# MultiChannelADC.net
KiCad netlist of a schematic drawn in Altium Designer
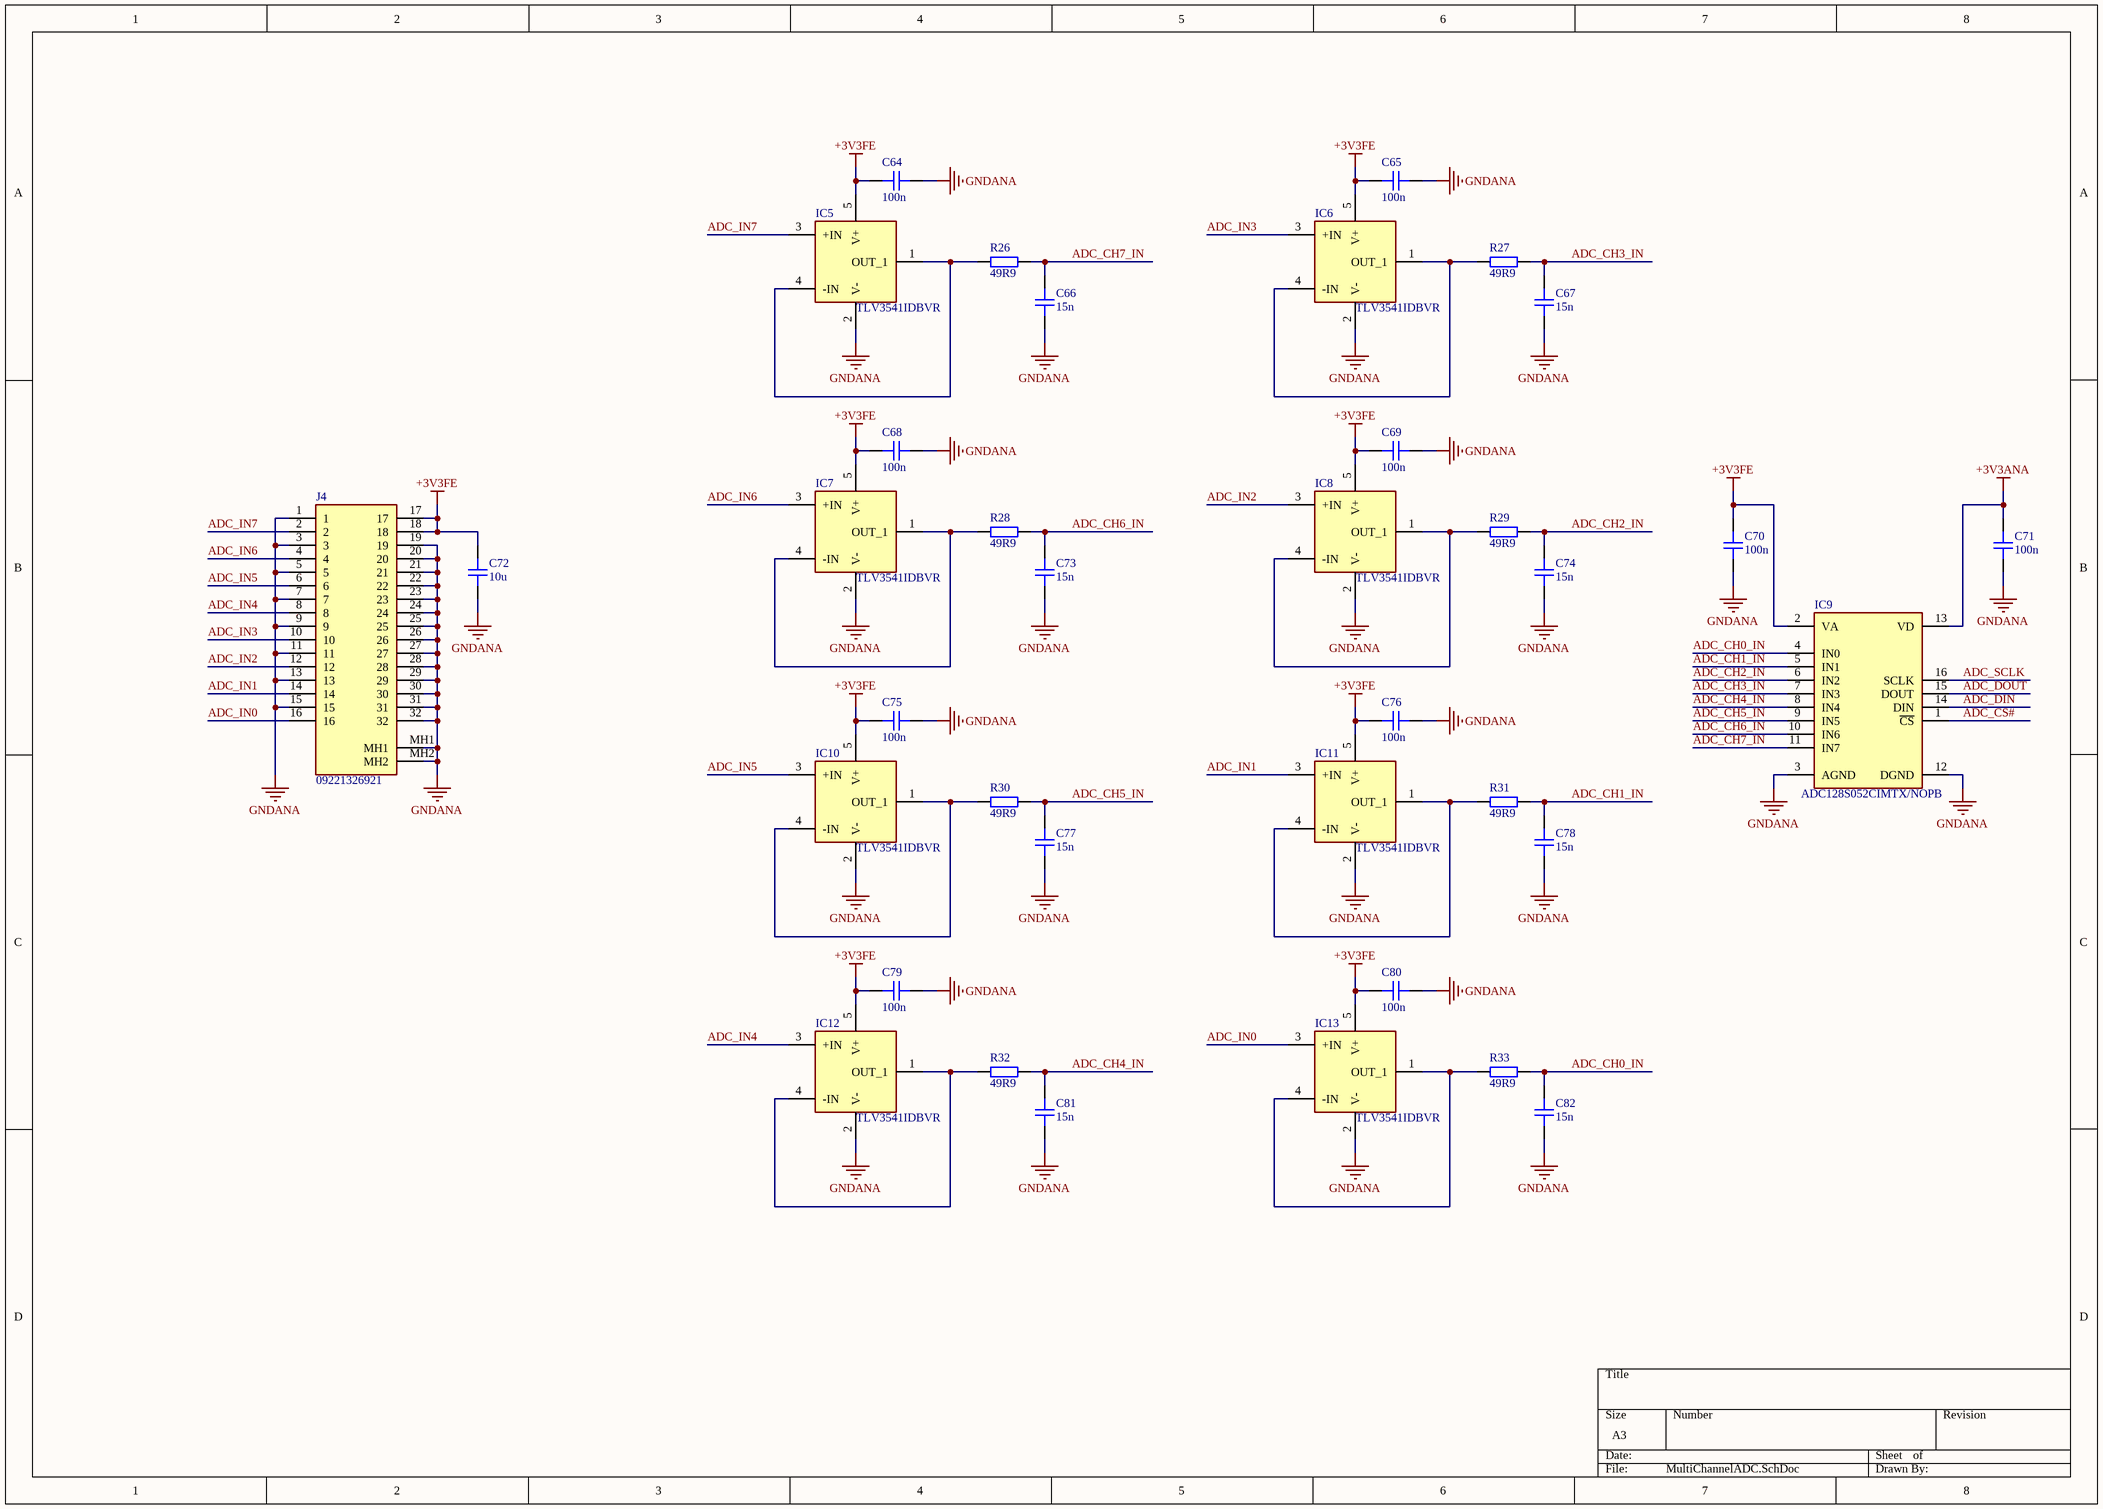
[diagram p0: MultiChannelADC.SchDoc]

(export (version "E")
  (design (tool "Eeschema 10.0.6"))
  (components
    (comp (ref "C64")
      (value "100n")
      (footprint "CAP_0402")
      (description "Capacitor SMD 0402")
      (libsource (lib "Schematic-Lib-PhilsLab") (part "CAP_0402"))
    )
    (comp (ref "C65")
      (value "100n")
      (footprint "CAP_0402")
      (description "Capacitor SMD 0402")
      (libsource (lib "Schematic-Lib-PhilsLab") (part "CAP_0402"))
    )
    (comp (ref "C66")
      (value "15n")
      (footprint "CAP_0402")
      (description "Capacitor SMD 0402")
      (libsource (lib "Schematic-Lib-PhilsLab") (part "CAP_0402"))
    )
    (comp (ref "C67")
      (value "15n")
      (footprint "CAP_0402")
      (description "Capacitor SMD 0402")
      (libsource (lib "Schematic-Lib-PhilsLab") (part "CAP_0402"))
    )
    (comp (ref "C68")
      (value "100n")
      (footprint "CAP_0402")
      (description "Capacitor SMD 0402")
      (libsource (lib "Schematic-Lib-PhilsLab") (part "CAP_0402"))
    )
    (comp (ref "C69")
      (value "100n")
      (footprint "CAP_0402")
      (description "Capacitor SMD 0402")
      (libsource (lib "Schematic-Lib-PhilsLab") (part "CAP_0402"))
    )
    (comp (ref "C70")
      (value "100n")
      (footprint "CAP_0402")
      (description "Capacitor SMD 0402")
      (libsource (lib "Schematic-Lib-PhilsLab") (part "CAP_0402"))
    )
    (comp (ref "C71")
      (value "100n")
      (footprint "CAP_0402")
      (description "Capacitor SMD 0402")
      (libsource (lib "Schematic-Lib-PhilsLab") (part "CAP_0402"))
    )
    (comp (ref "C72")
      (value "10u")
      (footprint "CAP_0603")
      (description "Capacitor SMD 0603")
      (libsource (lib "Schematic-Lib-PhilsLab") (part "CAP_0603"))
    )
    (comp (ref "C73")
      (value "15n")
      (footprint "CAP_0402")
      (description "Capacitor SMD 0402")
      (libsource (lib "Schematic-Lib-PhilsLab") (part "CAP_0402"))
    )
    (comp (ref "C74")
      (value "15n")
      (footprint "CAP_0402")
      (description "Capacitor SMD 0402")
      (libsource (lib "Schematic-Lib-PhilsLab") (part "CAP_0402"))
    )
    (comp (ref "C75")
      (value "100n")
      (footprint "CAP_0402")
      (description "Capacitor SMD 0402")
      (libsource (lib "Schematic-Lib-PhilsLab") (part "CAP_0402"))
    )
    (comp (ref "C76")
      (value "100n")
      (footprint "CAP_0402")
      (description "Capacitor SMD 0402")
      (libsource (lib "Schematic-Lib-PhilsLab") (part "CAP_0402"))
    )
    (comp (ref "C77")
      (value "15n")
      (footprint "CAP_0402")
      (description "Capacitor SMD 0402")
      (libsource (lib "Schematic-Lib-PhilsLab") (part "CAP_0402"))
    )
    (comp (ref "C78")
      (value "15n")
      (footprint "CAP_0402")
      (description "Capacitor SMD 0402")
      (libsource (lib "Schematic-Lib-PhilsLab") (part "CAP_0402"))
    )
    (comp (ref "C79")
      (value "100n")
      (footprint "CAP_0402")
      (description "Capacitor SMD 0402")
      (libsource (lib "Schematic-Lib-PhilsLab") (part "CAP_0402"))
    )
    (comp (ref "C80")
      (value "100n")
      (footprint "CAP_0402")
      (description "Capacitor SMD 0402")
      (libsource (lib "Schematic-Lib-PhilsLab") (part "CAP_0402"))
    )
    (comp (ref "C81")
      (value "15n")
      (footprint "CAP_0402")
      (description "Capacitor SMD 0402")
      (libsource (lib "Schematic-Lib-PhilsLab") (part "CAP_0402"))
    )
    (comp (ref "C82")
      (value "15n")
      (footprint "CAP_0402")
      (description "Capacitor SMD 0402")
      (libsource (lib "Schematic-Lib-PhilsLab") (part "CAP_0402"))
    )
    (comp (ref "IC5")
      (value "TLV3541IDBVR")
      (footprint "Footprint-Lib-PhilsLab:SOT95P280X145-5N - duplicate")
      (description "Integrated Circuit")
      (fields (field (name "MOUSER PART NUMBER") "595-TLV3541IDBVR"))
      (libsource (lib "Schematic-Lib-PhilsLab") (part "TLV3541IDBVR"))
    )
    (comp (ref "IC6")
      (value "TLV3541IDBVR")
      (footprint "Footprint-Lib-PhilsLab:SOT95P280X145-5N - duplicate")
      (description "Integrated Circuit")
      (fields (field (name "MOUSER PART NUMBER") "595-TLV3541IDBVR"))
      (libsource (lib "Schematic-Lib-PhilsLab") (part "TLV3541IDBVR"))
    )
    (comp (ref "IC7")
      (value "TLV3541IDBVR")
      (footprint "Footprint-Lib-PhilsLab:SOT95P280X145-5N - duplicate")
      (description "Integrated Circuit")
      (fields (field (name "MOUSER PART NUMBER") "595-TLV3541IDBVR"))
      (libsource (lib "Schematic-Lib-PhilsLab") (part "TLV3541IDBVR"))
    )
    (comp (ref "IC8")
      (value "TLV3541IDBVR")
      (footprint "Footprint-Lib-PhilsLab:SOT95P280X145-5N - duplicate")
      (description "Integrated Circuit")
      (fields (field (name "MOUSER PART NUMBER") "595-TLV3541IDBVR"))
      (libsource (lib "Schematic-Lib-PhilsLab") (part "TLV3541IDBVR"))
    )
    (comp (ref "IC9")
      (value "ADC128S052CIMTX/NOPB")
      (footprint "Footprint-Lib-PhilsLab:SOP65P640X120-16N")
      (description "Texas Instruments 8 Channel A/D-Converter 500 kSP/S")
      (fields (field (name "MOUSER PART NUMBER") "926-A128S052CIMTXNPB"))
      (libsource (lib "Schematic-Lib-PhilsLab") (part "ADC128S052CIMTX/NOPB"))
    )
    (comp (ref "IC10")
      (value "TLV3541IDBVR")
      (footprint "Footprint-Lib-PhilsLab:SOT95P280X145-5N - duplicate")
      (description "Integrated Circuit")
      (fields (field (name "MOUSER PART NUMBER") "595-TLV3541IDBVR"))
      (libsource (lib "Schematic-Lib-PhilsLab") (part "TLV3541IDBVR"))
    )
    (comp (ref "IC11")
      (value "TLV3541IDBVR")
      (footprint "Footprint-Lib-PhilsLab:SOT95P280X145-5N - duplicate")
      (description "Integrated Circuit")
      (fields (field (name "MOUSER PART NUMBER") "595-TLV3541IDBVR"))
      (libsource (lib "Schematic-Lib-PhilsLab") (part "TLV3541IDBVR"))
    )
    (comp (ref "IC12")
      (value "TLV3541IDBVR")
      (footprint "Footprint-Lib-PhilsLab:SOT95P280X145-5N - duplicate")
      (description "Integrated Circuit")
      (fields (field (name "MOUSER PART NUMBER") "595-TLV3541IDBVR"))
      (libsource (lib "Schematic-Lib-PhilsLab") (part "TLV3541IDBVR"))
    )
    (comp (ref "IC13")
      (value "TLV3541IDBVR")
      (footprint "Footprint-Lib-PhilsLab:SOT95P280X145-5N - duplicate")
      (description "Integrated Circuit")
      (fields (field (name "MOUSER PART NUMBER") "595-TLV3541IDBVR"))
      (libsource (lib "Schematic-Lib-PhilsLab") (part "TLV3541IDBVR"))
    )
    (comp (ref "J4")
      (value "09221326921")
      (footprint "Footprint-Lib-PhilsLab:09221326921")
      (description "Connector")
      (fields (field (name "MOUSER PART NUMBER") "617-09-22-132-6921"))
      (libsource (lib "Schematic-Lib-PhilsLab") (part "09221326921"))
    )
    (comp (ref "R26")
      (value "49R9")
      (footprint "RES_0402")
      (description "Resistor SMD 0402")
      (libsource (lib "Schematic-Lib-PhilsLab") (part "RES_0402"))
    )
    (comp (ref "R27")
      (value "49R9")
      (footprint "RES_0402")
      (description "Resistor SMD 0402")
      (libsource (lib "Schematic-Lib-PhilsLab") (part "RES_0402"))
    )
    (comp (ref "R28")
      (value "49R9")
      (footprint "RES_0402")
      (description "Resistor SMD 0402")
      (libsource (lib "Schematic-Lib-PhilsLab") (part "RES_0402"))
    )
    (comp (ref "R29")
      (value "49R9")
      (footprint "RES_0402")
      (description "Resistor SMD 0402")
      (libsource (lib "Schematic-Lib-PhilsLab") (part "RES_0402"))
    )
    (comp (ref "R30")
      (value "49R9")
      (footprint "RES_0402")
      (description "Resistor SMD 0402")
      (libsource (lib "Schematic-Lib-PhilsLab") (part "RES_0402"))
    )
    (comp (ref "R31")
      (value "49R9")
      (footprint "RES_0402")
      (description "Resistor SMD 0402")
      (libsource (lib "Schematic-Lib-PhilsLab") (part "RES_0402"))
    )
    (comp (ref "R32")
      (value "49R9")
      (footprint "RES_0402")
      (description "Resistor SMD 0402")
      (libsource (lib "Schematic-Lib-PhilsLab") (part "RES_0402"))
    )
    (comp (ref "R33")
      (value "49R9")
      (footprint "RES_0402")
      (description "Resistor SMD 0402")
      (libsource (lib "Schematic-Lib-PhilsLab") (part "RES_0402"))
    )
  )
  (nets
    (net (code "1") (name "+3V3ANA") (class "Default")
      (node (ref "C71") (pin "2") (pinfunction "2_2") (pintype "passive"))
      (node (ref "IC9") (pin "13") (pinfunction "VD_13") (pintype "passive"))
    )
    (net (code "2") (name "+3V3FE") (class "Default")
      (node (ref "C64") (pin "2") (pinfunction "2_2") (pintype "passive"))
      (node (ref "C65") (pin "2") (pinfunction "2_2") (pintype "passive"))
      (node (ref "C68") (pin "2") (pinfunction "2_2") (pintype "passive"))
      (node (ref "C69") (pin "2") (pinfunction "2_2") (pintype "passive"))
      (node (ref "C70") (pin "2") (pinfunction "2_2") (pintype "passive"))
      (node (ref "C72") (pin "2") (pinfunction "2_2") (pintype "passive"))
      (node (ref "C75") (pin "2") (pinfunction "2_2") (pintype "passive"))
      (node (ref "C76") (pin "2") (pinfunction "2_2") (pintype "passive"))
      (node (ref "C79") (pin "2") (pinfunction "2_2") (pintype "passive"))
      (node (ref "C80") (pin "2") (pinfunction "2_2") (pintype "passive"))
      (node (ref "IC10") (pin "5") (pinfunction "V+_5") (pintype "passive"))
      (node (ref "IC11") (pin "5") (pinfunction "V+_5") (pintype "passive"))
      (node (ref "IC12") (pin "5") (pinfunction "V+_5") (pintype "passive"))
      (node (ref "IC13") (pin "5") (pinfunction "V+_5") (pintype "passive"))
      (node (ref "IC5") (pin "5") (pinfunction "V+_5") (pintype "passive"))
      (node (ref "IC6") (pin "5") (pinfunction "V+_5") (pintype "passive"))
      (node (ref "IC7") (pin "5") (pinfunction "V+_5") (pintype "passive"))
      (node (ref "IC8") (pin "5") (pinfunction "V+_5") (pintype "passive"))
      (node (ref "IC9") (pin "2") (pinfunction "VA_2") (pintype "passive"))
      (node (ref "J4") (pin "17") (pinfunction "17_17") (pintype "passive"))
      (node (ref "J4") (pin "18") (pinfunction "18_18") (pintype "passive"))
    )
    (net (code "3") (name "/ADC_CH0_IN") (class "Default")
      (node (ref "C82") (pin "2") (pinfunction "2_2") (pintype "passive"))
      (node (ref "IC9") (pin "4") (pinfunction "IN0_4") (pintype "passive"))
      (node (ref "R33") (pin "2") (pinfunction "2_2") (pintype "passive"))
    )
    (net (code "4") (name "/ADC_CH1_IN") (class "Default")
      (node (ref "C78") (pin "2") (pinfunction "2_2") (pintype "passive"))
      (node (ref "IC9") (pin "5") (pinfunction "IN1_5") (pintype "passive"))
      (node (ref "R31") (pin "2") (pinfunction "2_2") (pintype "passive"))
    )
    (net (code "5") (name "/ADC_CH2_IN") (class "Default")
      (node (ref "C74") (pin "2") (pinfunction "2_2") (pintype "passive"))
      (node (ref "IC9") (pin "6") (pinfunction "IN2_6") (pintype "passive"))
      (node (ref "R29") (pin "2") (pinfunction "2_2") (pintype "passive"))
    )
    (net (code "6") (name "/ADC_CH3_IN") (class "Default")
      (node (ref "C67") (pin "2") (pinfunction "2_2") (pintype "passive"))
      (node (ref "IC9") (pin "7") (pinfunction "IN3_7") (pintype "passive"))
      (node (ref "R27") (pin "2") (pinfunction "2_2") (pintype "passive"))
    )
    (net (code "7") (name "/ADC_CH4_IN") (class "Default")
      (node (ref "C81") (pin "2") (pinfunction "2_2") (pintype "passive"))
      (node (ref "IC9") (pin "8") (pinfunction "IN4_8") (pintype "passive"))
      (node (ref "R32") (pin "2") (pinfunction "2_2") (pintype "passive"))
    )
    (net (code "8") (name "/ADC_CH5_IN") (class "Default")
      (node (ref "C77") (pin "2") (pinfunction "2_2") (pintype "passive"))
      (node (ref "IC9") (pin "9") (pinfunction "IN5_9") (pintype "passive"))
      (node (ref "R30") (pin "2") (pinfunction "2_2") (pintype "passive"))
    )
    (net (code "9") (name "/ADC_CH6_IN") (class "Default")
      (node (ref "C73") (pin "2") (pinfunction "2_2") (pintype "passive"))
      (node (ref "IC9") (pin "10") (pinfunction "IN6_10") (pintype "passive"))
      (node (ref "R28") (pin "2") (pinfunction "2_2") (pintype "passive"))
    )
    (net (code "10") (name "/ADC_CH7_IN") (class "Default")
      (node (ref "C66") (pin "2") (pinfunction "2_2") (pintype "passive"))
      (node (ref "IC9") (pin "11") (pinfunction "IN7_11") (pintype "passive"))
      (node (ref "R26") (pin "2") (pinfunction "2_2") (pintype "passive"))
    )
    (net (code "11") (name "/ADC_CS#") (class "Default")
      (node (ref "IC9") (pin "1") (pinfunction "~{CS}_1") (pintype "passive"))
    )
    (net (code "12") (name "/ADC_DIN") (class "Default")
      (node (ref "IC9") (pin "14") (pinfunction "DIN_14") (pintype "passive"))
    )
    (net (code "13") (name "/ADC_DOUT") (class "Default")
      (node (ref "IC9") (pin "15") (pinfunction "DOUT_15") (pintype "passive"))
    )
    (net (code "14") (name "/ADC_IN0") (class "Default")
      (node (ref "IC13") (pin "3") (pinfunction "+IN_3") (pintype "passive"))
      (node (ref "J4") (pin "16") (pinfunction "16_16") (pintype "passive"))
    )
    (net (code "15") (name "/ADC_IN1") (class "Default")
      (node (ref "IC11") (pin "3") (pinfunction "+IN_3") (pintype "passive"))
      (node (ref "J4") (pin "14") (pinfunction "14_14") (pintype "passive"))
    )
    (net (code "16") (name "/ADC_IN2") (class "Default")
      (node (ref "IC8") (pin "3") (pinfunction "+IN_3") (pintype "passive"))
      (node (ref "J4") (pin "12") (pinfunction "12_12") (pintype "passive"))
    )
    (net (code "17") (name "/ADC_IN3") (class "Default")
      (node (ref "IC6") (pin "3") (pinfunction "+IN_3") (pintype "passive"))
      (node (ref "J4") (pin "10") (pinfunction "10_10") (pintype "passive"))
    )
    (net (code "18") (name "/ADC_IN4") (class "Default")
      (node (ref "IC12") (pin "3") (pinfunction "+IN_3") (pintype "passive"))
      (node (ref "J4") (pin "8") (pinfunction "8_8") (pintype "passive"))
    )
    (net (code "19") (name "/ADC_IN5") (class "Default")
      (node (ref "IC10") (pin "3") (pinfunction "+IN_3") (pintype "passive"))
      (node (ref "J4") (pin "6") (pinfunction "6_6") (pintype "passive"))
    )
    (net (code "20") (name "/ADC_IN6") (class "Default")
      (node (ref "IC7") (pin "3") (pinfunction "+IN_3") (pintype "passive"))
      (node (ref "J4") (pin "4") (pinfunction "4_4") (pintype "passive"))
    )
    (net (code "21") (name "/ADC_IN7") (class "Default")
      (node (ref "IC5") (pin "3") (pinfunction "+IN_3") (pintype "passive"))
      (node (ref "J4") (pin "2") (pinfunction "2_2") (pintype "passive"))
    )
    (net (code "22") (name "/ADC_SCLK") (class "Default")
      (node (ref "IC9") (pin "16") (pinfunction "SCLK_16") (pintype "passive"))
    )
    (net (code "23") (name "GNDANA") (class "Default")
      (node (ref "C64") (pin "1") (pinfunction "1_1") (pintype "passive"))
      (node (ref "C65") (pin "1") (pinfunction "1_1") (pintype "passive"))
      (node (ref "C66") (pin "1") (pinfunction "1_1") (pintype "passive"))
      (node (ref "C67") (pin "1") (pinfunction "1_1") (pintype "passive"))
      (node (ref "C68") (pin "1") (pinfunction "1_1") (pintype "passive"))
      (node (ref "C69") (pin "1") (pinfunction "1_1") (pintype "passive"))
      (node (ref "C70") (pin "1") (pinfunction "1_1") (pintype "passive"))
      (node (ref "C71") (pin "1") (pinfunction "1_1") (pintype "passive"))
      (node (ref "C72") (pin "1") (pinfunction "1_1") (pintype "passive"))
      (node (ref "C73") (pin "1") (pinfunction "1_1") (pintype "passive"))
      (node (ref "C74") (pin "1") (pinfunction "1_1") (pintype "passive"))
      (node (ref "C75") (pin "1") (pinfunction "1_1") (pintype "passive"))
      (node (ref "C76") (pin "1") (pinfunction "1_1") (pintype "passive"))
      (node (ref "C77") (pin "1") (pinfunction "1_1") (pintype "passive"))
      (node (ref "C78") (pin "1") (pinfunction "1_1") (pintype "passive"))
      (node (ref "C79") (pin "1") (pinfunction "1_1") (pintype "passive"))
      (node (ref "C80") (pin "1") (pinfunction "1_1") (pintype "passive"))
      (node (ref "C81") (pin "1") (pinfunction "1_1") (pintype "passive"))
      (node (ref "C82") (pin "1") (pinfunction "1_1") (pintype "passive"))
      (node (ref "IC10") (pin "2") (pinfunction "V-_2") (pintype "passive"))
      (node (ref "IC11") (pin "2") (pinfunction "V-_2") (pintype "passive"))
      (node (ref "IC12") (pin "2") (pinfunction "V-_2") (pintype "passive"))
      (node (ref "IC13") (pin "2") (pinfunction "V-_2") (pintype "passive"))
      (node (ref "IC5") (pin "2") (pinfunction "V-_2") (pintype "passive"))
      (node (ref "IC6") (pin "2") (pinfunction "V-_2") (pintype "passive"))
      (node (ref "IC7") (pin "2") (pinfunction "V-_2") (pintype "passive"))
      (node (ref "IC8") (pin "2") (pinfunction "V-_2") (pintype "passive"))
      (node (ref "IC9") (pin "12") (pinfunction "DGND_12") (pintype "passive"))
      (node (ref "IC9") (pin "3") (pinfunction "AGND_3") (pintype "passive"))
      (node (ref "J4") (pin "1") (pinfunction "1_1") (pintype "passive"))
      (node (ref "J4") (pin "11") (pinfunction "11_11") (pintype "passive"))
      (node (ref "J4") (pin "13") (pinfunction "13_13") (pintype "passive"))
      (node (ref "J4") (pin "15") (pinfunction "15_15") (pintype "passive"))
      (node (ref "J4") (pin "19") (pinfunction "19_19") (pintype "passive"))
      (node (ref "J4") (pin "20") (pinfunction "20_20") (pintype "passive"))
      (node (ref "J4") (pin "21") (pinfunction "21_21") (pintype "passive"))
      (node (ref "J4") (pin "22") (pinfunction "22_22") (pintype "passive"))
      (node (ref "J4") (pin "23") (pinfunction "23_23") (pintype "passive"))
      (node (ref "J4") (pin "24") (pinfunction "24_24") (pintype "passive"))
      (node (ref "J4") (pin "25") (pinfunction "25_25") (pintype "passive"))
      (node (ref "J4") (pin "26") (pinfunction "26_26") (pintype "passive"))
      (node (ref "J4") (pin "27") (pinfunction "27_27") (pintype "passive"))
      (node (ref "J4") (pin "28") (pinfunction "28_28") (pintype "passive"))
      (node (ref "J4") (pin "29") (pinfunction "29_29") (pintype "passive"))
      (node (ref "J4") (pin "3") (pinfunction "3_3") (pintype "passive"))
      (node (ref "J4") (pin "30") (pinfunction "30_30") (pintype "passive"))
      (node (ref "J4") (pin "31") (pinfunction "31_31") (pintype "passive"))
      (node (ref "J4") (pin "32") (pinfunction "32_32") (pintype "passive"))
      (node (ref "J4") (pin "5") (pinfunction "5_5") (pintype "passive"))
      (node (ref "J4") (pin "7") (pinfunction "7_7") (pintype "passive"))
      (node (ref "J4") (pin "9") (pinfunction "9_9") (pintype "passive"))
      (node (ref "J4") (pin "MH1") (pinfunction "MH1_MH1") (pintype "passive"))
      (node (ref "J4") (pin "MH2") (pinfunction "MH2_MH2") (pintype "passive"))
    )
    (net (code "24") (name "Net-(IC5--IN)") (class "Default")
      (node (ref "IC5") (pin "1") (pinfunction "OUT_1_1") (pintype "passive"))
      (node (ref "IC5") (pin "4") (pinfunction "-IN_4") (pintype "passive"))
      (node (ref "R26") (pin "1") (pinfunction "1_1") (pintype "passive"))
    )
    (net (code "25") (name "Net-(IC6--IN)") (class "Default")
      (node (ref "IC6") (pin "1") (pinfunction "OUT_1_1") (pintype "passive"))
      (node (ref "IC6") (pin "4") (pinfunction "-IN_4") (pintype "passive"))
      (node (ref "R27") (pin "1") (pinfunction "1_1") (pintype "passive"))
    )
    (net (code "26") (name "Net-(IC7--IN)") (class "Default")
      (node (ref "IC7") (pin "1") (pinfunction "OUT_1_1") (pintype "passive"))
      (node (ref "IC7") (pin "4") (pinfunction "-IN_4") (pintype "passive"))
      (node (ref "R28") (pin "1") (pinfunction "1_1") (pintype "passive"))
    )
    (net (code "27") (name "Net-(IC8--IN)") (class "Default")
      (node (ref "IC8") (pin "1") (pinfunction "OUT_1_1") (pintype "passive"))
      (node (ref "IC8") (pin "4") (pinfunction "-IN_4") (pintype "passive"))
      (node (ref "R29") (pin "1") (pinfunction "1_1") (pintype "passive"))
    )
    (net (code "28") (name "Net-(IC10--IN)") (class "Default")
      (node (ref "IC10") (pin "1") (pinfunction "OUT_1_1") (pintype "passive"))
      (node (ref "IC10") (pin "4") (pinfunction "-IN_4") (pintype "passive"))
      (node (ref "R30") (pin "1") (pinfunction "1_1") (pintype "passive"))
    )
    (net (code "29") (name "Net-(IC11--IN)") (class "Default")
      (node (ref "IC11") (pin "1") (pinfunction "OUT_1_1") (pintype "passive"))
      (node (ref "IC11") (pin "4") (pinfunction "-IN_4") (pintype "passive"))
      (node (ref "R31") (pin "1") (pinfunction "1_1") (pintype "passive"))
    )
    (net (code "30") (name "Net-(IC12--IN)") (class "Default")
      (node (ref "IC12") (pin "1") (pinfunction "OUT_1_1") (pintype "passive"))
      (node (ref "IC12") (pin "4") (pinfunction "-IN_4") (pintype "passive"))
      (node (ref "R32") (pin "1") (pinfunction "1_1") (pintype "passive"))
    )
    (net (code "31") (name "Net-(IC13--IN)") (class "Default")
      (node (ref "IC13") (pin "1") (pinfunction "OUT_1_1") (pintype "passive"))
      (node (ref "IC13") (pin "4") (pinfunction "-IN_4") (pintype "passive"))
      (node (ref "R33") (pin "1") (pinfunction "1_1") (pintype "passive"))
    )
  )
)
